# Base_v8.net
KiCad netlist of a schematic drawn in EAGLE
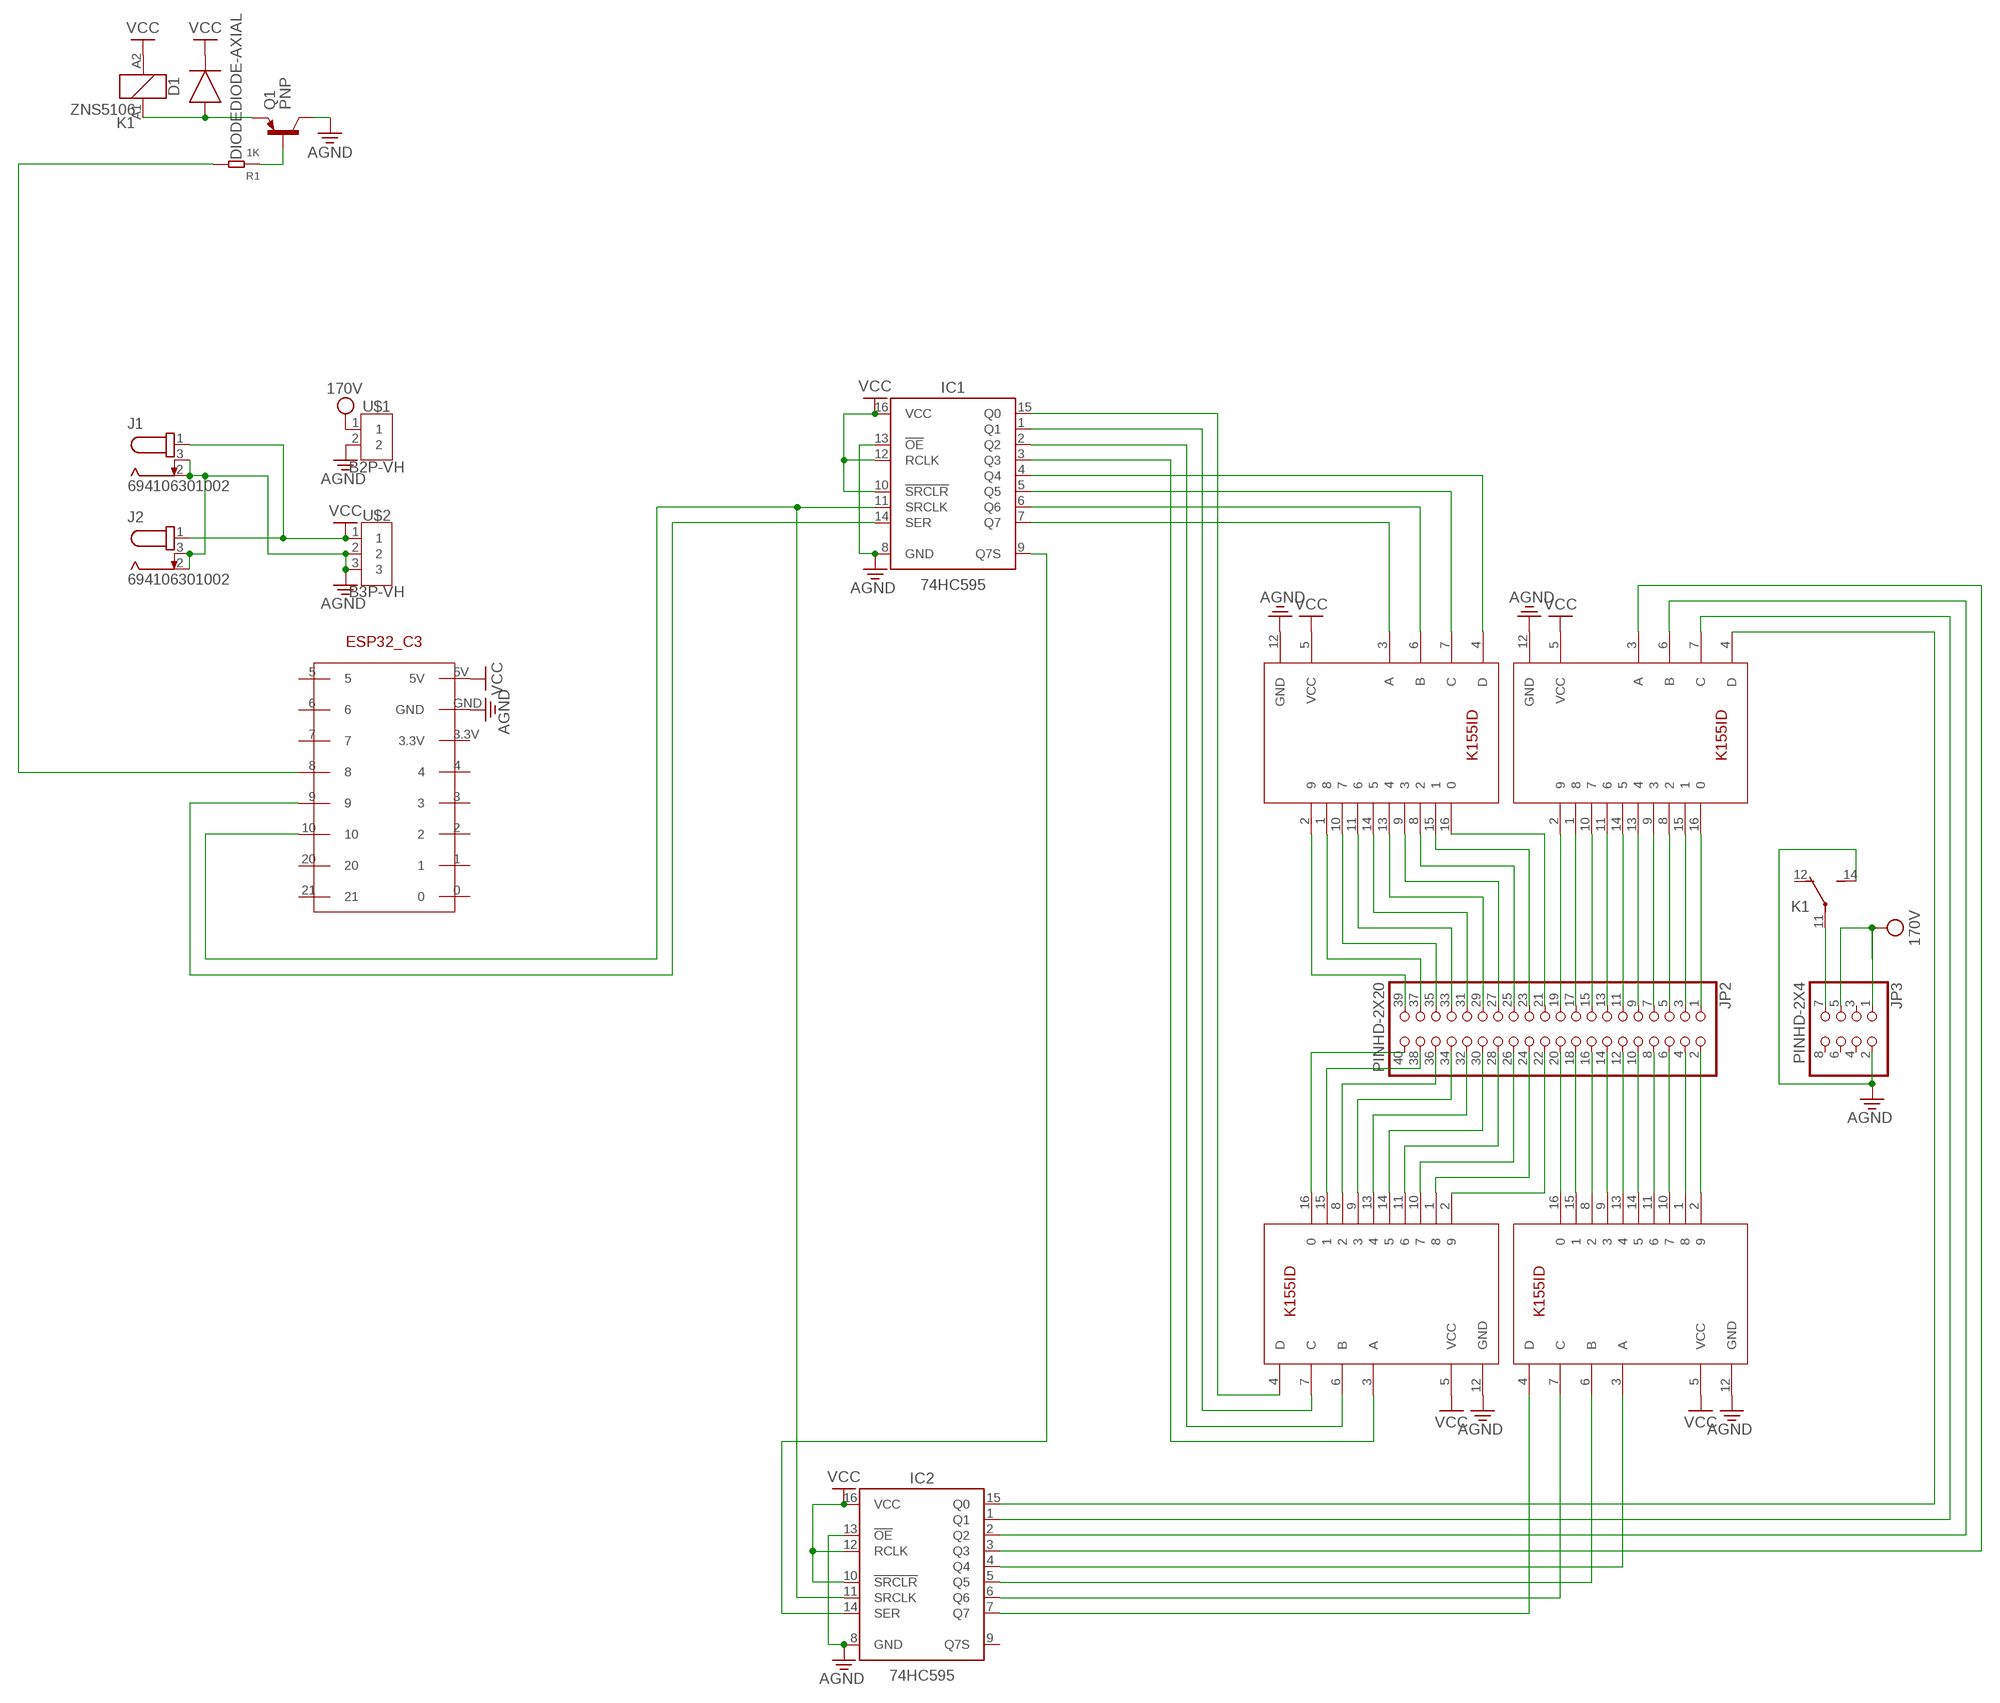
[diagram p0: schematic, sheet 1]

(export (version "E")
  (design (tool "Eeschema 10.0.6"))
  (components
    (comp (ref "D1")
      (value "DIODEDIODE-AXIAL")
      (footprint "eagle-import:DIODE-AXIAL")
      (libsource (lib "eagle-import") (part "DIODEDIODE-AXIAL"))
    )
    (comp (ref "IC1")
      (value "74HC595")
      (footprint "eagle-import:DIP762W53P254L1969H508Q16B")
      (fields (field (name "MANUFACTURER") "Generic"))
      (libsource (lib "eagle-import") (part "74HC595_PDIP"))
    )
    (comp (ref "IC2")
      (value "74HC595")
      (footprint "eagle-import:DIP762W53P254L1969H508Q16B")
      (fields (field (name "MANUFACTURER") "Generic"))
      (libsource (lib "eagle-import") (part "74HC595_PDIP"))
    )
    (comp (ref "IC3")
      (value "K155ID")
      (footprint "eagle-import:K155ID")
      (libsource (lib "eagle-import") (part "K155ID"))
    )
    (comp (ref "IC4")
      (value "K155ID")
      (footprint "eagle-import:K155ID")
      (libsource (lib "eagle-import") (part "K155ID"))
    )
    (comp (ref "IC5")
      (value "K155ID")
      (footprint "eagle-import:K155ID")
      (libsource (lib "eagle-import") (part "K155ID"))
    )
    (comp (ref "IC6")
      (value "K155ID")
      (footprint "eagle-import:K155ID")
      (libsource (lib "eagle-import") (part "K155ID"))
    )
    (comp (ref "J1")
      (value "694106301002")
      (footprint "eagle-import:694106301002")
      (fields
        (field (name "DIGIKEY_PART_NUMBER") "732-5930-ND")
        (field (name "MANUFACTURER") "Wurth Electronics Inc.")
        (field (name "CREATED_BY") "PCBLayout.com")
      )
      (libsource (lib "eagle-import") (part "694106301002"))
    )
    (comp (ref "J2")
      (value "694106301002")
      (footprint "eagle-import:694106301002")
      (fields
        (field (name "DIGIKEY_PART_NUMBER") "732-5930-ND")
        (field (name "MANUFACTURER") "Wurth Electronics Inc.")
        (field (name "CREATED_BY") "PCBLayout.com")
      )
      (libsource (lib "eagle-import") (part "694106301002"))
    )
    (comp (ref "JP2")
      (value "PINHD-2X20")
      (footprint "eagle-import:2X20")
      (fields (field (name "MANUFACTURER") "Generic"))
      (libsource (lib "eagle-import") (part "PINHD-2X20"))
    )
    (comp (ref "JP3")
      (value "PINHD-2X4")
      (footprint "eagle-import:2X04")
      (fields (field (name "MANUFACTURER") "Generic"))
      (libsource (lib "eagle-import") (part "PINHD-2X4"))
    )
    (comp (ref "K1")
      (value "ZNS5106")
      (footprint "eagle-import:ZN5")
      (libsource (lib "eagle-import") (part "ZNS5106"))
    )
    (comp (ref "Q1")
      (value "PNP")
      (footprint "eagle-import:TO92")
      (libsource (lib "eagle-import") (part "PNPTO92-CBE_"))
    )
    (comp (ref "R1")
      (value "1K")
      (footprint "eagle-import:PR-D2.3XL6.5MM")
      (fields (field (name "MPN") "FHCFR-1/4W-102J"))
      (libsource (lib "eagle-import") (part "DIP-RES-1K-5%-1/4W(PR-D2.3XL6.5MM)"))
    )
    (comp (ref "U$1")
      (value "B2P-VH")
      (footprint "eagle-import:B2P-VH_396-2N")
      (fields (field (name "MANUFACTURER") " JST Sales America Inc."))
      (libsource (lib "eagle-import") (part "B2P-VH"))
    )
    (comp (ref "U$2")
      (value "B3P-VH")
      (footprint "eagle-import:B3P-VH_396_3N")
      (fields (field (name "MANUFACTURER") " JST Sales America Inc."))
      (libsource (lib "eagle-import") (part "B3P-VH"))
    )
    (comp (ref "U$5")
      (value "ESP32_C3_SUPERMINI")
      (footprint "eagle-import:ESP32_C3_SUPERMINI")
      (libsource (lib "eagle-import") (part "ESP32_C3_SUPERMINI"))
    )
  )
  (nets
    (net (code "1") (name "170V") (class "Default")
      (node (ref "JP3") (pin "1") (pinfunction "1_1") (pintype "passive"))
      (node (ref "JP3") (pin "5") (pinfunction "5_5") (pintype "passive"))
      (node (ref "U$1") (pin "1") (pinfunction "1_1") (pintype "bidirectional"))
    )
    (net (code "2") (name "AGND") (class "Default")
      (node (ref "IC1") (pin "13") (pinfunction "~{OE}_13") (pintype "output"))
      (node (ref "IC1") (pin "8") (pinfunction "GND_8") (pintype "bidirectional"))
      (node (ref "IC2") (pin "13") (pinfunction "~{OE}_13") (pintype "output"))
      (node (ref "IC2") (pin "8") (pinfunction "GND_8") (pintype "bidirectional"))
      (node (ref "IC3") (pin "12") (pinfunction "GND_12") (pintype "bidirectional"))
      (node (ref "IC4") (pin "12") (pinfunction "GND_12") (pintype "bidirectional"))
      (node (ref "IC5") (pin "12") (pinfunction "GND_12") (pintype "bidirectional"))
      (node (ref "IC6") (pin "12") (pinfunction "GND_12") (pintype "bidirectional"))
      (node (ref "J1") (pin "2") (pinfunction "2_2") (pintype "passive"))
      (node (ref "J1") (pin "3") (pinfunction "3_3") (pintype "passive"))
      (node (ref "J2") (pin "2") (pinfunction "2_2") (pintype "passive"))
      (node (ref "J2") (pin "3") (pinfunction "3_3") (pintype "passive"))
      (node (ref "JP3") (pin "2") (pinfunction "2_2") (pintype "passive"))
      (node (ref "K1") (pin "14") (pinfunction "S_14") (pintype "passive"))
      (node (ref "Q1") (pin "1") (pinfunction "C_1") (pintype "passive"))
      (node (ref "U$1") (pin "2") (pinfunction "2_2") (pintype "bidirectional"))
      (node (ref "U$2") (pin "2") (pinfunction "2_2") (pintype "bidirectional"))
      (node (ref "U$2") (pin "3") (pinfunction "3_3") (pintype "bidirectional"))
      (node (ref "U$5") (pin "GND") (pinfunction "GND_GND") (pintype "bidirectional"))
    )
    (net (code "3") (name "Net-(D1-A)") (class "Default")
      (node (ref "D1") (pin "1") (pinfunction "A_1") (pintype "passive"))
      (node (ref "K1") (pin "A1") (pinfunction "1_A1") (pintype "passive"))
      (node (ref "Q1") (pin "3") (pinfunction "E_3") (pintype "passive"))
    )
    (net (code "4") (name "Net-(IC1-Q0)") (class "Default")
      (node (ref "IC1") (pin "15") (pinfunction "Q0_15") (pintype "output"))
      (node (ref "IC4") (pin "4") (pinfunction "D_4") (pintype "bidirectional"))
    )
    (net (code "5") (name "Net-(IC1-Q1)") (class "Default")
      (node (ref "IC1") (pin "1") (pinfunction "Q1_1") (pintype "output"))
      (node (ref "IC4") (pin "7") (pinfunction "C_7") (pintype "bidirectional"))
    )
    (net (code "6") (name "Net-(IC1-Q2)") (class "Default")
      (node (ref "IC1") (pin "2") (pinfunction "Q2_2") (pintype "output"))
      (node (ref "IC4") (pin "6") (pinfunction "B_6") (pintype "bidirectional"))
    )
    (net (code "7") (name "Net-(IC1-Q3)") (class "Default")
      (node (ref "IC1") (pin "3") (pinfunction "Q3_3") (pintype "output"))
      (node (ref "IC4") (pin "3") (pinfunction "A_3") (pintype "bidirectional"))
    )
    (net (code "8") (name "Net-(IC1-Q4)") (class "Default")
      (node (ref "IC1") (pin "4") (pinfunction "Q4_4") (pintype "output"))
      (node (ref "IC3") (pin "4") (pinfunction "D_4") (pintype "bidirectional"))
    )
    (net (code "9") (name "Net-(IC1-Q5)") (class "Default")
      (node (ref "IC1") (pin "5") (pinfunction "Q5_5") (pintype "output"))
      (node (ref "IC3") (pin "7") (pinfunction "C_7") (pintype "bidirectional"))
    )
    (net (code "10") (name "Net-(IC1-Q6)") (class "Default")
      (node (ref "IC1") (pin "6") (pinfunction "Q6_6") (pintype "output"))
      (node (ref "IC3") (pin "6") (pinfunction "B_6") (pintype "bidirectional"))
    )
    (net (code "11") (name "Net-(IC1-Q7)") (class "Default")
      (node (ref "IC1") (pin "7") (pinfunction "Q7_7") (pintype "output"))
      (node (ref "IC3") (pin "3") (pinfunction "A_3") (pintype "bidirectional"))
    )
    (net (code "12") (name "Net-(IC1-Q7S)") (class "Default")
      (node (ref "IC1") (pin "9") (pinfunction "Q7S_9") (pintype "output"))
      (node (ref "IC2") (pin "14") (pinfunction "SER_14") (pintype "input"))
    )
    (net (code "13") (name "Net-(IC1-SER)") (class "Default")
      (node (ref "IC1") (pin "14") (pinfunction "SER_14") (pintype "input"))
      (node (ref "U$5") (pin "9") (pinfunction "9_9") (pintype "bidirectional"))
    )
    (net (code "14") (name "Net-(IC1-SRCLK)") (class "Default")
      (node (ref "IC1") (pin "11") (pinfunction "SRCLK_11") (pintype "input"))
      (node (ref "IC2") (pin "11") (pinfunction "SRCLK_11") (pintype "input"))
      (node (ref "U$5") (pin "10") (pinfunction "10_10") (pintype "bidirectional"))
    )
    (net (code "15") (name "Net-(IC2-Q0)") (class "Default")
      (node (ref "IC2") (pin "15") (pinfunction "Q0_15") (pintype "output"))
      (node (ref "IC5") (pin "4") (pinfunction "D_4") (pintype "bidirectional"))
    )
    (net (code "16") (name "Net-(IC2-Q1)") (class "Default")
      (node (ref "IC2") (pin "1") (pinfunction "Q1_1") (pintype "output"))
      (node (ref "IC5") (pin "7") (pinfunction "C_7") (pintype "bidirectional"))
    )
    (net (code "17") (name "Net-(IC2-Q2)") (class "Default")
      (node (ref "IC2") (pin "2") (pinfunction "Q2_2") (pintype "output"))
      (node (ref "IC5") (pin "6") (pinfunction "B_6") (pintype "bidirectional"))
    )
    (net (code "18") (name "Net-(IC2-Q3)") (class "Default")
      (node (ref "IC2") (pin "3") (pinfunction "Q3_3") (pintype "output"))
      (node (ref "IC5") (pin "3") (pinfunction "A_3") (pintype "bidirectional"))
    )
    (net (code "19") (name "Net-(IC2-Q4)") (class "Default")
      (node (ref "IC2") (pin "4") (pinfunction "Q4_4") (pintype "output"))
      (node (ref "IC6") (pin "3") (pinfunction "A_3") (pintype "bidirectional"))
    )
    (net (code "20") (name "Net-(IC2-Q5)") (class "Default")
      (node (ref "IC2") (pin "5") (pinfunction "Q5_5") (pintype "output"))
      (node (ref "IC6") (pin "6") (pinfunction "B_6") (pintype "bidirectional"))
    )
    (net (code "21") (name "Net-(IC2-Q6)") (class "Default")
      (node (ref "IC2") (pin "6") (pinfunction "Q6_6") (pintype "output"))
      (node (ref "IC6") (pin "7") (pinfunction "C_7") (pintype "bidirectional"))
    )
    (net (code "22") (name "Net-(IC2-Q7)") (class "Default")
      (node (ref "IC2") (pin "7") (pinfunction "Q7_7") (pintype "output"))
      (node (ref "IC6") (pin "4") (pinfunction "D_4") (pintype "bidirectional"))
    )
    (net (code "23") (name "Net-(IC3-0)") (class "Default")
      (node (ref "IC3") (pin "16") (pinfunction "0_16") (pintype "bidirectional"))
      (node (ref "JP2") (pin "21") (pinfunction "21_21") (pintype "passive"))
    )
    (net (code "24") (name "Net-(IC3-1)") (class "Default")
      (node (ref "IC3") (pin "15") (pinfunction "1_15") (pintype "bidirectional"))
      (node (ref "JP2") (pin "23") (pinfunction "23_23") (pintype "passive"))
    )
    (net (code "25") (name "Net-(IC3-2)") (class "Default")
      (node (ref "IC3") (pin "8") (pinfunction "2_8") (pintype "bidirectional"))
      (node (ref "JP2") (pin "25") (pinfunction "25_25") (pintype "passive"))
    )
    (net (code "26") (name "Net-(IC3-3)") (class "Default")
      (node (ref "IC3") (pin "9") (pinfunction "3_9") (pintype "bidirectional"))
      (node (ref "JP2") (pin "27") (pinfunction "27_27") (pintype "passive"))
    )
    (net (code "27") (name "Net-(IC3-4)") (class "Default")
      (node (ref "IC3") (pin "13") (pinfunction "4_13") (pintype "bidirectional"))
      (node (ref "JP2") (pin "29") (pinfunction "29_29") (pintype "passive"))
    )
    (net (code "28") (name "Net-(IC3-5)") (class "Default")
      (node (ref "IC3") (pin "14") (pinfunction "5_14") (pintype "bidirectional"))
      (node (ref "JP2") (pin "31") (pinfunction "31_31") (pintype "passive"))
    )
    (net (code "29") (name "Net-(IC3-6)") (class "Default")
      (node (ref "IC3") (pin "11") (pinfunction "6_11") (pintype "bidirectional"))
      (node (ref "JP2") (pin "33") (pinfunction "33_33") (pintype "passive"))
    )
    (net (code "30") (name "Net-(IC3-7)") (class "Default")
      (node (ref "IC3") (pin "10") (pinfunction "7_10") (pintype "bidirectional"))
      (node (ref "JP2") (pin "35") (pinfunction "35_35") (pintype "passive"))
    )
    (net (code "31") (name "Net-(IC3-8)") (class "Default")
      (node (ref "IC3") (pin "1") (pinfunction "8_1") (pintype "bidirectional"))
      (node (ref "JP2") (pin "37") (pinfunction "37_37") (pintype "passive"))
    )
    (net (code "32") (name "Net-(IC3-9)") (class "Default")
      (node (ref "IC3") (pin "2") (pinfunction "9_2") (pintype "bidirectional"))
      (node (ref "JP2") (pin "39") (pinfunction "39_39") (pintype "passive"))
    )
    (net (code "33") (name "Net-(IC4-0)") (class "Default")
      (node (ref "IC4") (pin "16") (pinfunction "0_16") (pintype "bidirectional"))
      (node (ref "JP2") (pin "40") (pinfunction "40_40") (pintype "passive"))
    )
    (net (code "34") (name "Net-(IC4-1)") (class "Default")
      (node (ref "IC4") (pin "15") (pinfunction "1_15") (pintype "bidirectional"))
      (node (ref "JP2") (pin "38") (pinfunction "38_38") (pintype "passive"))
    )
    (net (code "35") (name "Net-(IC4-2)") (class "Default")
      (node (ref "IC4") (pin "8") (pinfunction "2_8") (pintype "bidirectional"))
      (node (ref "JP2") (pin "36") (pinfunction "36_36") (pintype "passive"))
    )
    (net (code "36") (name "Net-(IC4-3)") (class "Default")
      (node (ref "IC4") (pin "9") (pinfunction "3_9") (pintype "bidirectional"))
      (node (ref "JP2") (pin "34") (pinfunction "34_34") (pintype "passive"))
    )
    (net (code "37") (name "Net-(IC4-4)") (class "Default")
      (node (ref "IC4") (pin "13") (pinfunction "4_13") (pintype "bidirectional"))
      (node (ref "JP2") (pin "32") (pinfunction "32_32") (pintype "passive"))
    )
    (net (code "38") (name "Net-(IC4-5)") (class "Default")
      (node (ref "IC4") (pin "14") (pinfunction "5_14") (pintype "bidirectional"))
      (node (ref "JP2") (pin "30") (pinfunction "30_30") (pintype "passive"))
    )
    (net (code "39") (name "Net-(IC4-6)") (class "Default")
      (node (ref "IC4") (pin "11") (pinfunction "6_11") (pintype "bidirectional"))
      (node (ref "JP2") (pin "28") (pinfunction "28_28") (pintype "passive"))
    )
    (net (code "40") (name "Net-(IC4-7)") (class "Default")
      (node (ref "IC4") (pin "10") (pinfunction "7_10") (pintype "bidirectional"))
      (node (ref "JP2") (pin "26") (pinfunction "26_26") (pintype "passive"))
    )
    (net (code "41") (name "Net-(IC4-8)") (class "Default")
      (node (ref "IC4") (pin "1") (pinfunction "8_1") (pintype "bidirectional"))
      (node (ref "JP2") (pin "24") (pinfunction "24_24") (pintype "passive"))
    )
    (net (code "42") (name "Net-(IC4-9)") (class "Default")
      (node (ref "IC4") (pin "2") (pinfunction "9_2") (pintype "bidirectional"))
      (node (ref "JP2") (pin "22") (pinfunction "22_22") (pintype "passive"))
    )
    (net (code "43") (name "Net-(IC5-0)") (class "Default")
      (node (ref "IC5") (pin "16") (pinfunction "0_16") (pintype "bidirectional"))
      (node (ref "JP2") (pin "1") (pinfunction "1_1") (pintype "passive"))
    )
    (net (code "44") (name "Net-(IC5-1)") (class "Default")
      (node (ref "IC5") (pin "15") (pinfunction "1_15") (pintype "bidirectional"))
      (node (ref "JP2") (pin "3") (pinfunction "3_3") (pintype "passive"))
    )
    (net (code "45") (name "Net-(IC5-2)") (class "Default")
      (node (ref "IC5") (pin "8") (pinfunction "2_8") (pintype "bidirectional"))
      (node (ref "JP2") (pin "5") (pinfunction "5_5") (pintype "passive"))
    )
    (net (code "46") (name "Net-(IC5-3)") (class "Default")
      (node (ref "IC5") (pin "9") (pinfunction "3_9") (pintype "bidirectional"))
      (node (ref "JP2") (pin "7") (pinfunction "7_7") (pintype "passive"))
    )
    (net (code "47") (name "Net-(IC5-4)") (class "Default")
      (node (ref "IC5") (pin "13") (pinfunction "4_13") (pintype "bidirectional"))
      (node (ref "JP2") (pin "9") (pinfunction "9_9") (pintype "passive"))
    )
    (net (code "48") (name "Net-(IC5-5)") (class "Default")
      (node (ref "IC5") (pin "14") (pinfunction "5_14") (pintype "bidirectional"))
      (node (ref "JP2") (pin "11") (pinfunction "11_11") (pintype "passive"))
    )
    (net (code "49") (name "Net-(IC5-6)") (class "Default")
      (node (ref "IC5") (pin "11") (pinfunction "6_11") (pintype "bidirectional"))
      (node (ref "JP2") (pin "13") (pinfunction "13_13") (pintype "passive"))
    )
    (net (code "50") (name "Net-(IC5-7)") (class "Default")
      (node (ref "IC5") (pin "10") (pinfunction "7_10") (pintype "bidirectional"))
      (node (ref "JP2") (pin "15") (pinfunction "15_15") (pintype "passive"))
    )
    (net (code "51") (name "Net-(IC5-8)") (class "Default")
      (node (ref "IC5") (pin "1") (pinfunction "8_1") (pintype "bidirectional"))
      (node (ref "JP2") (pin "17") (pinfunction "17_17") (pintype "passive"))
    )
    (net (code "52") (name "Net-(IC5-9)") (class "Default")
      (node (ref "IC5") (pin "2") (pinfunction "9_2") (pintype "bidirectional"))
      (node (ref "JP2") (pin "19") (pinfunction "19_19") (pintype "passive"))
    )
    (net (code "53") (name "Net-(IC6-0)") (class "Default")
      (node (ref "IC6") (pin "16") (pinfunction "0_16") (pintype "bidirectional"))
      (node (ref "JP2") (pin "20") (pinfunction "20_20") (pintype "passive"))
    )
    (net (code "54") (name "Net-(IC6-1)") (class "Default")
      (node (ref "IC6") (pin "15") (pinfunction "1_15") (pintype "bidirectional"))
      (node (ref "JP2") (pin "18") (pinfunction "18_18") (pintype "passive"))
    )
    (net (code "55") (name "Net-(IC6-2)") (class "Default")
      (node (ref "IC6") (pin "8") (pinfunction "2_8") (pintype "bidirectional"))
      (node (ref "JP2") (pin "16") (pinfunction "16_16") (pintype "passive"))
    )
    (net (code "56") (name "Net-(IC6-3)") (class "Default")
      (node (ref "IC6") (pin "9") (pinfunction "3_9") (pintype "bidirectional"))
      (node (ref "JP2") (pin "14") (pinfunction "14_14") (pintype "passive"))
    )
    (net (code "57") (name "Net-(IC6-4)") (class "Default")
      (node (ref "IC6") (pin "13") (pinfunction "4_13") (pintype "bidirectional"))
      (node (ref "JP2") (pin "12") (pinfunction "12_12") (pintype "passive"))
    )
    (net (code "58") (name "Net-(IC6-5)") (class "Default")
      (node (ref "IC6") (pin "14") (pinfunction "5_14") (pintype "bidirectional"))
      (node (ref "JP2") (pin "10") (pinfunction "10_10") (pintype "passive"))
    )
    (net (code "59") (name "Net-(IC6-6)") (class "Default")
      (node (ref "IC6") (pin "11") (pinfunction "6_11") (pintype "bidirectional"))
      (node (ref "JP2") (pin "8") (pinfunction "8_8") (pintype "passive"))
    )
    (net (code "60") (name "Net-(IC6-7)") (class "Default")
      (node (ref "IC6") (pin "10") (pinfunction "7_10") (pintype "bidirectional"))
      (node (ref "JP2") (pin "6") (pinfunction "6_6") (pintype "passive"))
    )
    (net (code "61") (name "Net-(IC6-8)") (class "Default")
      (node (ref "IC6") (pin "1") (pinfunction "8_1") (pintype "bidirectional"))
      (node (ref "JP2") (pin "4") (pinfunction "4_4") (pintype "passive"))
    )
    (net (code "62") (name "Net-(IC6-9)") (class "Default")
      (node (ref "IC6") (pin "2") (pinfunction "9_2") (pintype "bidirectional"))
      (node (ref "JP2") (pin "2") (pinfunction "2_2") (pintype "passive"))
    )
    (net (code "63") (name "Net-(K1B-P)") (class "Default")
      (node (ref "JP3") (pin "7") (pinfunction "7_7") (pintype "passive"))
      (node (ref "K1") (pin "11") (pinfunction "P_11") (pintype "passive"))
    )
    (net (code "64") (name "Net-(Q1-B)") (class "Default")
      (node (ref "Q1") (pin "2") (pinfunction "B_2") (pintype "passive"))
      (node (ref "R1") (pin "1") (pinfunction "1_1") (pintype "passive"))
    )
    (net (code "65") (name "Net-(R1-Pad2)") (class "Default")
      (node (ref "R1") (pin "2") (pinfunction "2_2") (pintype "passive"))
      (node (ref "U$5") (pin "8") (pinfunction "8_8") (pintype "bidirectional"))
    )
    (net (code "66") (name "VCC") (class "Default")
      (node (ref "D1") (pin "2") (pinfunction "C_2") (pintype "passive"))
      (node (ref "IC1") (pin "10") (pinfunction "~{SRCLR}_10") (pintype "input"))
      (node (ref "IC1") (pin "12") (pinfunction "RCLK_12") (pintype "input"))
      (node (ref "IC1") (pin "16") (pinfunction "VCC_16") (pintype "bidirectional"))
      (node (ref "IC2") (pin "10") (pinfunction "~{SRCLR}_10") (pintype "input"))
      (node (ref "IC2") (pin "12") (pinfunction "RCLK_12") (pintype "input"))
      (node (ref "IC2") (pin "16") (pinfunction "VCC_16") (pintype "bidirectional"))
      (node (ref "IC3") (pin "5") (pinfunction "VCC_5") (pintype "bidirectional"))
      (node (ref "IC4") (pin "5") (pinfunction "VCC_5") (pintype "bidirectional"))
      (node (ref "IC5") (pin "5") (pinfunction "VCC_5") (pintype "bidirectional"))
      (node (ref "IC6") (pin "5") (pinfunction "VCC_5") (pintype "bidirectional"))
      (node (ref "J1") (pin "1") (pinfunction "1_1") (pintype "passive"))
      (node (ref "J2") (pin "1") (pinfunction "1_1") (pintype "passive"))
      (node (ref "K1") (pin "A2") (pinfunction "2_A2") (pintype "passive"))
      (node (ref "U$2") (pin "1") (pinfunction "1_1") (pintype "bidirectional"))
      (node (ref "U$5") (pin "5V") (pinfunction "5V_5V") (pintype "bidirectional"))
    )
    (net (code "67") (name "unconnected-(IC2-Q7S-Pad9)") (class "Default")
      (node (ref "IC2") (pin "9") (pinfunction "Q7S_9") (pintype "output"))
    )
    (net (code "68") (name "unconnected-(JP3-Pad3)") (class "Default")
      (node (ref "JP3") (pin "3") (pinfunction "3_3") (pintype "passive"))
    )
    (net (code "69") (name "unconnected-(JP3-Pad4)") (class "Default")
      (node (ref "JP3") (pin "4") (pinfunction "4_4") (pintype "passive"))
    )
    (net (code "70") (name "unconnected-(JP3-Pad6)") (class "Default")
      (node (ref "JP3") (pin "6") (pinfunction "6_6") (pintype "passive"))
    )
    (net (code "71") (name "unconnected-(JP3-Pad8)") (class "Default")
      (node (ref "JP3") (pin "8") (pinfunction "8_8") (pintype "passive"))
    )
    (net (code "72") (name "unconnected-(K1B-O-Pad12)") (class "Default")
      (node (ref "K1") (pin "12") (pinfunction "O_12") (pintype "passive"))
    )
    (net (code "73") (name "unconnected-(U$5-Pad0)") (class "Default")
      (node (ref "U$5") (pin "0") (pinfunction "0_0") (pintype "bidirectional"))
    )
    (net (code "74") (name "unconnected-(U$5-Pad1)") (class "Default")
      (node (ref "U$5") (pin "1") (pinfunction "1_1") (pintype "bidirectional"))
    )
    (net (code "75") (name "unconnected-(U$5-Pad2)") (class "Default")
      (node (ref "U$5") (pin "2") (pinfunction "2_2") (pintype "bidirectional"))
    )
    (net (code "76") (name "unconnected-(U$5-Pad3)") (class "Default")
      (node (ref "U$5") (pin "3") (pinfunction "3_3") (pintype "bidirectional"))
    )
    (net (code "77") (name "unconnected-(U$5-Pad3.3V)") (class "Default")
      (node (ref "U$5") (pin "3.3V") (pinfunction "3.3V_3.3V") (pintype "bidirectional"))
    )
    (net (code "78") (name "unconnected-(U$5-Pad4)") (class "Default")
      (node (ref "U$5") (pin "4") (pinfunction "4_4") (pintype "bidirectional"))
    )
    (net (code "79") (name "unconnected-(U$5-Pad5)") (class "Default")
      (node (ref "U$5") (pin "5") (pinfunction "5_5") (pintype "bidirectional"))
    )
    (net (code "80") (name "unconnected-(U$5-Pad6)") (class "Default")
      (node (ref "U$5") (pin "6") (pinfunction "6_6") (pintype "bidirectional"))
    )
    (net (code "81") (name "unconnected-(U$5-Pad7)") (class "Default")
      (node (ref "U$5") (pin "7") (pinfunction "7_7") (pintype "bidirectional"))
    )
    (net (code "82") (name "unconnected-(U$5-Pad20)") (class "Default")
      (node (ref "U$5") (pin "20") (pinfunction "20_20") (pintype "bidirectional"))
    )
    (net (code "83") (name "unconnected-(U$5-Pad21)") (class "Default")
      (node (ref "U$5") (pin "21") (pinfunction "21_21") (pintype "bidirectional"))
    )
  )
)
